# licht.net
KiCad netlist of a schematic drawn in EAGLE
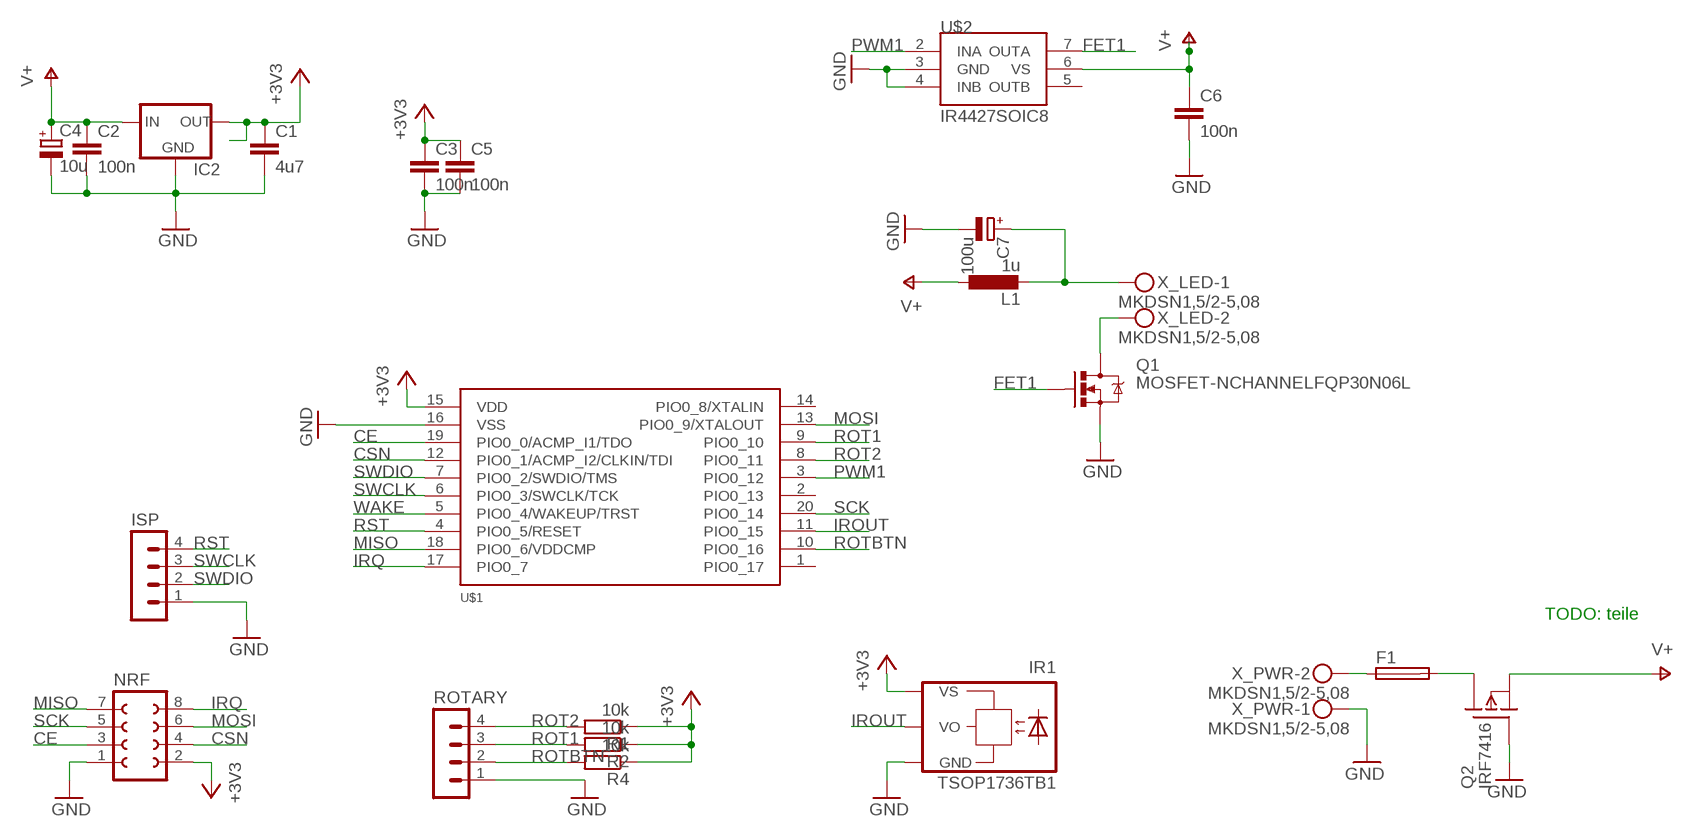
[diagram p0: schematic, sheet 1]

(export (version "E")
  (design (tool "Eeschema 10.0.6"))
  (components
    (comp (ref "C1")
      (value "4u7")
      (footprint "eagle-import:C0805")
      (libsource (lib "eagle-import") (part "C-EUC0805"))
    )
    (comp (ref "C2")
      (value "100n")
      (footprint "eagle-import:C0805")
      (libsource (lib "eagle-import") (part "C-EUC0805"))
    )
    (comp (ref "C3")
      (value "100n")
      (footprint "eagle-import:C0805")
      (libsource (lib "eagle-import") (part "C-EUC0805"))
    )
    (comp (ref "C4")
      (value "10u")
      (footprint "eagle-import:E2,5-6")
      (libsource (lib "eagle-import") (part "rcl_CPOL-EUE2.5-6"))
    )
    (comp (ref "C5")
      (value "100n")
      (footprint "eagle-import:C0805")
      (libsource (lib "eagle-import") (part "C-EUC0805"))
    )
    (comp (ref "C6")
      (value "100n")
      (footprint "eagle-import:C0805")
      (libsource (lib "eagle-import") (part "C-EUC0805"))
    )
    (comp (ref "C7")
      (value "100u")
      (footprint "eagle-import:E2,5-5")
      (libsource (lib "eagle-import") (part "CPOL-EUE2.5-5"))
    )
    (comp (ref "F1")
      (value "PTF45")
      (footprint "eagle-import:PTF45")
      (libsource (lib "eagle-import") (part "PTF45"))
    )
    (comp (ref "IC2")
      (value "TS2940")
      (footprint "eagle-import:TO252")
      (libsource (lib "eagle-import") (part "TS2940"))
    )
    (comp (ref "IR1")
      (value "TSOP1736TB1")
      (footprint "eagle-import:TSOP17_TB1")
      (libsource (lib "eagle-import") (part "TSOP17TB136"))
    )
    (comp (ref "ISP")
      (value "MA04-1")
      (footprint "eagle-import:MA04-1")
      (libsource (lib "eagle-import") (part "MA04-1"))
    )
    (comp (ref "L1")
      (value "1u")
      (footprint "eagle-import:PISR-BIGPAD")
      (libsource (lib "eagle-import") (part "L-EUPISR-BIGPAD"))
    )
    (comp (ref "NRF")
      (value "FE04-2")
      (footprint "eagle-import:FE04-2")
      (libsource (lib "eagle-import") (part "FE04-2"))
    )
    (comp (ref "Q1")
      (value "MOSFET-NCHANNELFQP30N06L")
      (footprint "eagle-import:TO220V")
      (libsource (lib "eagle-import") (part "MOSFET-NCHANNELFQP30N06L"))
    )
    (comp (ref "Q2")
      (value "IRF7416")
      (footprint "eagle-import:SO8")
      (libsource (lib "eagle-import") (part "IRF7205"))
    )
    (comp (ref "R1")
      (value "10k")
      (footprint "eagle-import:R0805")
      (libsource (lib "eagle-import") (part "R-EU_R0805"))
    )
    (comp (ref "R2")
      (value "10k")
      (footprint "eagle-import:R0805")
      (libsource (lib "eagle-import") (part "R-EU_R0805"))
    )
    (comp (ref "R4")
      (value "10k")
      (footprint "eagle-import:R0805")
      (libsource (lib "eagle-import") (part "R-EU_R0805"))
    )
    (comp (ref "ROTARY")
      (value "MA04-1")
      (footprint "eagle-import:MA04-1")
      (libsource (lib "eagle-import") (part "MA04-1"))
    )
    (comp (ref "U$1")
      (value "LPC812M101JD20")
      (footprint "eagle-import:SOIC20WIDE")
      (libsource (lib "eagle-import") (part "LPC812M101JD20"))
    )
    (comp (ref "U$2")
      (value "IR4427SOIC8")
      (footprint "eagle-import:SOIC8")
      (libsource (lib "eagle-import") (part "IR4427SOIC8"))
    )
    (comp (ref "X_LED")
      (value "MKDSN1,5/2-5,08")
      (footprint "eagle-import:MKDSN1,5_2-5,08")
      (fields (field (name "MPN") "MKDSN 1,5/2-5.08"))
      (libsource (lib "eagle-import") (part "MKDSN1,5/2-5,08"))
    )
    (comp (ref "X_PWR")
      (value "MKDSN1,5/2-5,08")
      (footprint "eagle-import:MKDSN1,5_2-5,08")
      (fields (field (name "MPN") "MKDSN 1,5/2-5.08"))
      (libsource (lib "eagle-import") (part "MKDSN1,5/2-5,08"))
    )
  )
  (nets
    (net (code "1") (name "+3V3") (class "Default")
      (node (ref "C1") (pin "1") (pinfunction "1_1") (pintype "passive"))
      (node (ref "C3") (pin "1") (pinfunction "1_1") (pintype "passive"))
      (node (ref "C5") (pin "1") (pinfunction "1_1") (pintype "passive"))
      (node (ref "IC2") (pin "3") (pinfunction "OUT_3") (pintype "passive"))
      (node (ref "IR1") (pin "VS") (pinfunction "VS_VS") (pintype "power_in"))
      (node (ref "NRF") (pin "2") (pinfunction "2_2") (pintype "passive"))
      (node (ref "R1") (pin "1") (pinfunction "1_1") (pintype "passive"))
      (node (ref "R2") (pin "1") (pinfunction "1_1") (pintype "passive"))
      (node (ref "R4") (pin "1") (pinfunction "1_1") (pintype "passive"))
      (node (ref "U$1") (pin "15") (pinfunction "VDD_15") (pintype "bidirectional"))
    )
    (net (code "2") (name "/CE") (class "Default")
      (node (ref "NRF") (pin "3") (pinfunction "3_3") (pintype "passive"))
      (node (ref "U$1") (pin "19") (pinfunction "PIO0_0/ACMP_I1/TDO_19") (pintype "bidirectional"))
    )
    (net (code "3") (name "/CSN") (class "Default")
      (node (ref "NRF") (pin "4") (pinfunction "4_4") (pintype "passive"))
      (node (ref "U$1") (pin "12") (pinfunction "PIO0_1/ACMP_I2/CLKIN/TDI_12") (pintype "bidirectional"))
    )
    (net (code "4") (name "/FET1") (class "Default")
      (node (ref "Q1") (pin "1") (pinfunction "G_1") (pintype "passive"))
      (node (ref "U$2") (pin "7") (pinfunction "OUTA_7") (pintype "bidirectional"))
    )
    (net (code "5") (name "/IROUT") (class "Default")
      (node (ref "IR1") (pin "VO") (pinfunction "VO_VO") (pintype "open_collector"))
      (node (ref "U$1") (pin "11") (pinfunction "PIO0_15_11") (pintype "bidirectional"))
    )
    (net (code "6") (name "/IRQ") (class "Default")
      (node (ref "NRF") (pin "8") (pinfunction "8_8") (pintype "passive"))
      (node (ref "U$1") (pin "17") (pinfunction "PIO0_7_17") (pintype "bidirectional"))
    )
    (net (code "7") (name "/MISO") (class "Default")
      (node (ref "NRF") (pin "7") (pinfunction "7_7") (pintype "passive"))
      (node (ref "U$1") (pin "18") (pinfunction "PIO0_6/VDDCMP_18") (pintype "bidirectional"))
    )
    (net (code "8") (name "/MOSI") (class "Default")
      (node (ref "NRF") (pin "6") (pinfunction "6_6") (pintype "passive"))
      (node (ref "U$1") (pin "13") (pinfunction "PIO0_9/XTALOUT_13") (pintype "bidirectional"))
    )
    (net (code "9") (name "/PWM1") (class "Default")
      (node (ref "U$1") (pin "3") (pinfunction "PIO0_12_3") (pintype "bidirectional"))
      (node (ref "U$2") (pin "2") (pinfunction "INA_2") (pintype "bidirectional"))
    )
    (net (code "10") (name "/ROT1") (class "Default")
      (node (ref "R2") (pin "2") (pinfunction "2_2") (pintype "passive"))
      (node (ref "ROTARY") (pin "3") (pinfunction "3_3") (pintype "passive"))
      (node (ref "U$1") (pin "9") (pinfunction "PIO0_10_9") (pintype "bidirectional"))
    )
    (net (code "11") (name "/ROT2") (class "Default")
      (node (ref "R1") (pin "2") (pinfunction "2_2") (pintype "passive"))
      (node (ref "ROTARY") (pin "4") (pinfunction "4_4") (pintype "passive"))
      (node (ref "U$1") (pin "8") (pinfunction "PIO0_11_8") (pintype "bidirectional"))
    )
    (net (code "12") (name "/ROTBTN") (class "Default")
      (node (ref "R4") (pin "2") (pinfunction "2_2") (pintype "passive"))
      (node (ref "ROTARY") (pin "2") (pinfunction "2_2") (pintype "passive"))
      (node (ref "U$1") (pin "10") (pinfunction "PIO0_16_10") (pintype "bidirectional"))
    )
    (net (code "13") (name "/RST") (class "Default")
      (node (ref "ISP") (pin "4") (pinfunction "4_4") (pintype "passive"))
      (node (ref "U$1") (pin "4") (pinfunction "PIO0_5/RESET_4") (pintype "bidirectional"))
    )
    (net (code "14") (name "/SCK") (class "Default")
      (node (ref "NRF") (pin "5") (pinfunction "5_5") (pintype "passive"))
      (node (ref "U$1") (pin "20") (pinfunction "PIO0_14_20") (pintype "bidirectional"))
    )
    (net (code "15") (name "/SWCLK") (class "Default")
      (node (ref "ISP") (pin "3") (pinfunction "3_3") (pintype "passive"))
      (node (ref "U$1") (pin "6") (pinfunction "PIO0_3/SWCLK/TCK_6") (pintype "bidirectional"))
    )
    (net (code "16") (name "/SWDIO") (class "Default")
      (node (ref "ISP") (pin "2") (pinfunction "2_2") (pintype "passive"))
      (node (ref "U$1") (pin "7") (pinfunction "PIO0_2/SWDIO/TMS_7") (pintype "bidirectional"))
    )
    (net (code "17") (name "/WAKE") (class "Default")
      (node (ref "U$1") (pin "5") (pinfunction "PIO0_4/WAKEUP/TRST_5") (pintype "bidirectional"))
    )
    (net (code "18") (name "GND") (class "Default")
      (node (ref "C1") (pin "2") (pinfunction "2_2") (pintype "passive"))
      (node (ref "C2") (pin "2") (pinfunction "2_2") (pintype "passive"))
      (node (ref "C3") (pin "2") (pinfunction "2_2") (pintype "passive"))
      (node (ref "C4") (pin "-") (pinfunction "-_-") (pintype "passive"))
      (node (ref "C5") (pin "2") (pinfunction "2_2") (pintype "passive"))
      (node (ref "C6") (pin "2") (pinfunction "2_2") (pintype "passive"))
      (node (ref "C7") (pin "-") (pinfunction "-_-") (pintype "passive"))
      (node (ref "IC2") (pin "2") (pinfunction "GND_2") (pintype "input"))
      (node (ref "IR1") (pin "GND") (pinfunction "GND_GND") (pintype "power_in"))
      (node (ref "ISP") (pin "1") (pinfunction "1_1") (pintype "passive"))
      (node (ref "NRF") (pin "1") (pinfunction "1_1") (pintype "passive"))
      (node (ref "Q1") (pin "3") (pinfunction "S_3") (pintype "passive"))
      (node (ref "Q2") (pin "4") (pinfunction "G_4") (pintype "passive"))
      (node (ref "ROTARY") (pin "1") (pinfunction "1_1") (pintype "passive"))
      (node (ref "U$1") (pin "16") (pinfunction "VSS_16") (pintype "bidirectional"))
      (node (ref "U$2") (pin "3") (pinfunction "GND_3") (pintype "bidirectional"))
      (node (ref "U$2") (pin "4") (pinfunction "INB_4") (pintype "bidirectional"))
      (node (ref "X_PWR") (pin "1") (pinfunction "KL_1") (pintype "passive"))
    )
    (net (code "19") (name "Net-(F1-Pad2)") (class "Default")
      (node (ref "F1") (pin "2") (pinfunction "2_2") (pintype "passive"))
      (node (ref "Q2") (pin "5") (pinfunction "D_5") (pintype "passive"))
      (node (ref "Q2") (pin "6") (pinfunction "D_6") (pintype "passive"))
      (node (ref "Q2") (pin "7") (pinfunction "D_7") (pintype "passive"))
      (node (ref "Q2") (pin "8") (pinfunction "D_8") (pintype "passive"))
    )
    (net (code "20") (name "Net-(Q1-D)") (class "Default")
      (node (ref "Q1") (pin "2") (pinfunction "D_2") (pintype "passive"))
      (node (ref "X_LED") (pin "2") (pinfunction "KL_2") (pintype "passive"))
    )
    (net (code "21") (name "Net-(X_LEDA-KL)") (class "Default")
      (node (ref "C7") (pin "+") (pinfunction "+_+") (pintype "passive"))
      (node (ref "L1") (pin "2") (pinfunction "2_2") (pintype "passive"))
      (node (ref "X_LED") (pin "1") (pinfunction "KL_1") (pintype "passive"))
    )
    (net (code "22") (name "Net-(X_PWRB-KL)") (class "Default")
      (node (ref "F1") (pin "1") (pinfunction "1_1") (pintype "passive"))
      (node (ref "X_PWR") (pin "2") (pinfunction "KL_2") (pintype "passive"))
    )
    (net (code "23") (name "V+") (class "Default")
      (node (ref "C2") (pin "1") (pinfunction "1_1") (pintype "passive"))
      (node (ref "C4") (pin "+") (pinfunction "+_+") (pintype "passive"))
      (node (ref "C6") (pin "1") (pinfunction "1_1") (pintype "passive"))
      (node (ref "IC2") (pin "1") (pinfunction "IN_1") (pintype "input"))
      (node (ref "L1") (pin "1") (pinfunction "1_1") (pintype "passive"))
      (node (ref "Q2") (pin "1") (pinfunction "S_1") (pintype "passive"))
      (node (ref "Q2") (pin "2") (pinfunction "S_2") (pintype "passive"))
      (node (ref "Q2") (pin "3") (pinfunction "S_3") (pintype "passive"))
      (node (ref "U$2") (pin "6") (pinfunction "VS_6") (pintype "bidirectional"))
    )
    (net (code "24") (name "unconnected-(U$1-PIO0_8{slash}XTALIN-Pad14)") (class "Default")
      (node (ref "U$1") (pin "14") (pinfunction "PIO0_8/XTALIN_14") (pintype "bidirectional"))
    )
    (net (code "25") (name "unconnected-(U$1-PIO0_13-Pad2)") (class "Default")
      (node (ref "U$1") (pin "2") (pinfunction "PIO0_13_2") (pintype "bidirectional"))
    )
    (net (code "26") (name "unconnected-(U$1-PIO0_17-Pad1)") (class "Default")
      (node (ref "U$1") (pin "1") (pinfunction "PIO0_17_1") (pintype "bidirectional"))
    )
    (net (code "27") (name "unconnected-(U$2-OUTB-Pad5)") (class "Default")
      (node (ref "U$2") (pin "5") (pinfunction "OUTB_5") (pintype "bidirectional"))
    )
  )
)
